# Mag_Enc_Sensors_muxed.net
KiCad netlist of a schematic drawn in Altium Designer
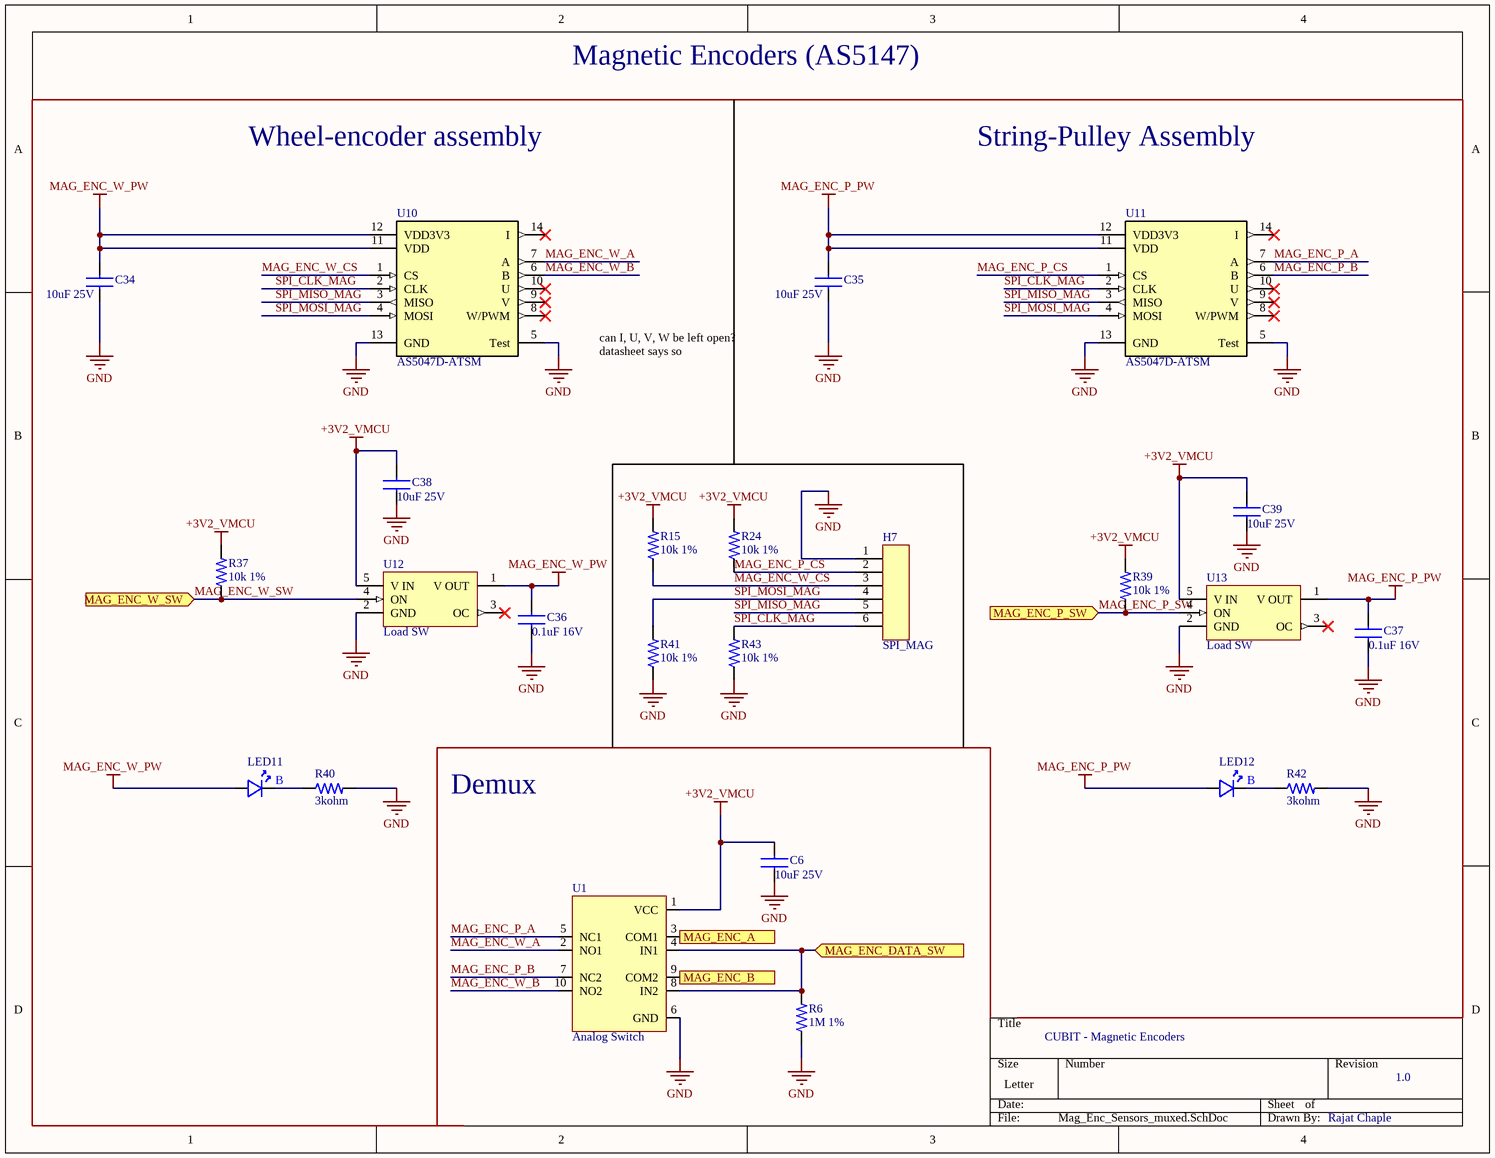
[diagram p0: Mag_Enc_Sensors_muxed.SchDoc]

(export (version "E")
  (design (tool "Eeschema 10.0.6"))
  (components
    (comp (ref "C6")
      (value "10uF 25V")
      (footprint "CAP_0805_02X125")
      (description "Cap 0805 25 V 10 uF ±20% Tolerance X5R Monolithic Ceramic Chip Capacitor")
      (fields
        (field (name "MANUFACTURER") "Murata")
        (field (name "MANUFACTURER PART NUMBER") "GRM21BR61E106KA73K")
      )
      (libsource (lib "LPEDT_proj_lib") (part "GRM21BR61E106KA73K"))
    )
    (comp (ref "C34")
      (value "10uF 25V")
      (footprint "CAP_0805_02X125")
      (description "Cap 0805 25 V 10 uF ±20% Tolerance X5R Monolithic Ceramic Chip Capacitor")
      (fields
        (field (name "MANUFACTURER") "Murata")
        (field (name "MANUFACTURER PART NUMBER") "GRM21BR61E106KA73K")
      )
      (libsource (lib "LPEDT_proj_lib") (part "GRM21BR61E106KA73K"))
    )
    (comp (ref "C35")
      (value "10uF 25V")
      (footprint "CAP_0805_02X125")
      (description "Cap 0805 25 V 10 uF ±20% Tolerance X5R Monolithic Ceramic Chip Capacitor")
      (fields
        (field (name "MANUFACTURER") "Murata")
        (field (name "MANUFACTURER PART NUMBER") "GRM21BR61E106KA73K")
      )
      (libsource (lib "LPEDT_proj_lib") (part "GRM21BR61E106KA73K"))
    )
    (comp (ref "C36")
      (value "0.1uF 16V")
      (footprint "CAP_0603_1MM")
      (description "Cap Ceramic 0.1uF 16V X7R 10% SMD 0603 125°C Paper T/R")
      (fields
        (field (name "MANUFACTURER") "KEMET")
        (field (name "MANUFACTURER PART NUMBER") "C0805C104K4RACAUTO")
      )
      (libsource (lib "LPEDT_proj_lib") (part "C0805C104K4RACAUTO"))
    )
    (comp (ref "C37")
      (value "0.1uF 16V")
      (footprint "CAP_0603_1MM")
      (description "Cap Ceramic 0.1uF 16V X7R 10% SMD 0603 125°C Paper T/R")
      (fields
        (field (name "MANUFACTURER") "KEMET")
        (field (name "MANUFACTURER PART NUMBER") "C0805C104K4RACAUTO")
      )
      (libsource (lib "LPEDT_proj_lib") (part "C0805C104K4RACAUTO"))
    )
    (comp (ref "C38")
      (value "10uF 25V")
      (footprint "CAP_0805_02X125")
      (description "Cap 0805 25 V 10 uF ±20% Tolerance X5R Monolithic Ceramic Chip Capacitor")
      (fields
        (field (name "MANUFACTURER") "Murata")
        (field (name "MANUFACTURER PART NUMBER") "GRM21BR61E106KA73K")
      )
      (libsource (lib "LPEDT_proj_lib") (part "GRM21BR61E106KA73K"))
    )
    (comp (ref "C39")
      (value "10uF 25V")
      (footprint "CAP_0805_02X125")
      (description "Cap 0805 25 V 10 uF ±20% Tolerance X5R Monolithic Ceramic Chip Capacitor")
      (fields
        (field (name "MANUFACTURER") "Murata")
        (field (name "MANUFACTURER PART NUMBER") "GRM21BR61E106KA73K")
      )
      (libsource (lib "LPEDT_proj_lib") (part "GRM21BR61E106KA73K"))
    )
    (comp (ref "H7")
      (value "SPI_MAG")
      (footprint "6_PIN_100MIL")
      (libsource (lib "LPEDT_proj_lib") (part "6_pin_connector"))
    )
    (comp (ref "LED11")
      (value "150060BS75000")
      (footprint "LED_0603_RED_WL-SMCW")
      (description "Led, Blue, 470 Nm, 3.2 V, 30 Ma, 145 Mcd Rohs Compliant: Yes")
      (fields (field (name "MANUFACTURER") "Wurth Electronics"))
      (libsource (lib "LPEDT_proj_lib") (part "150060BS75000"))
    )
    (comp (ref "LED12")
      (value "150060BS75000")
      (footprint "LED_0603_RED_WL-SMCW")
      (description "Led, Blue, 470 Nm, 3.2 V, 30 Ma, 145 Mcd Rohs Compliant: Yes")
      (fields (field (name "MANUFACTURER") "Wurth Electronics"))
      (libsource (lib "LPEDT_proj_lib") (part "150060BS75000"))
    )
    (comp (ref "R6")
      (value "1M 1%")
      (footprint "2_Chip_0603_RMCF")
      (description "Res 1M Ohm 1% 1/10W ±100ppm/°C Molded SMD Paper T/R")
      (fields
        (field (name "MANUFACTURER") "Stackpole Electronics")
        (field (name "MANUFACTURER PART NUMBER") "RMCF0603FT1M00")
      )
      (libsource (lib "LPEDT_proj_lib") (part "RMCF0603FT1M00"))
    )
    (comp (ref "R15")
      (value "10k 1%")
      (footprint "2_Chip_0603_RMCF")
      (description "Res 10K Ohm 1% 1/10W ±100ppm/°C Molded SMD SMD Paper T/R")
      (fields
        (field (name "MANUFACTURER") "Stackpole Electronics")
        (field (name "MANUFACTURER PART NUMBER") "RMCF0603FT10K0")
      )
      (libsource (lib "LPEDT_proj_lib") (part "RMCF0603FT10K0"))
    )
    (comp (ref "R24")
      (value "10k 1%")
      (footprint "2_Chip_0603_RMCF")
      (description "Res 10K Ohm 1% 1/10W ±100ppm/°C Molded SMD SMD Paper T/R")
      (fields
        (field (name "MANUFACTURER") "Stackpole Electronics")
        (field (name "MANUFACTURER PART NUMBER") "RMCF0603FT10K0")
      )
      (libsource (lib "LPEDT_proj_lib") (part "RMCF0603FT10K0"))
    )
    (comp (ref "R37")
      (value "10k 1%")
      (footprint "2_Chip_0603_RMCF")
      (description "Res 10K Ohm 1% 1/10W ±100ppm/°C Molded SMD SMD Paper T/R")
      (fields
        (field (name "MANUFACTURER") "Stackpole Electronics")
        (field (name "MANUFACTURER PART NUMBER") "RMCF0603FT10K0")
      )
      (libsource (lib "LPEDT_proj_lib") (part "RMCF0603FT10K0"))
    )
    (comp (ref "R39")
      (value "10k 1%")
      (footprint "2_Chip_0603_RMCF")
      (description "Res 10K Ohm 1% 1/10W ±100ppm/°C Molded SMD SMD Paper T/R")
      (fields
        (field (name "MANUFACTURER") "Stackpole Electronics")
        (field (name "MANUFACTURER PART NUMBER") "RMCF0603FT10K0")
      )
      (libsource (lib "LPEDT_proj_lib") (part "RMCF0603FT10K0"))
    )
    (comp (ref "R40")
      (value "3kohm")
      (footprint "CAP_0603_1MM")
      (description "Res 3000Ω ± 1.00% 0.1W ± 100ppm/℃ 0603")
      (fields
        (field (name "MANUFACTURER") "Yageo")
        (field (name "MANUFACTURER PART NUMBER") "RC0603FR-073KL")
      )
      (libsource (lib "LPEDT_proj_lib") (part "RC0603FR-073KL"))
    )
    (comp (ref "R41")
      (value "10k 1%")
      (footprint "2_Chip_0603_RMCF")
      (description "Res 10K Ohm 1% 1/10W ±100ppm/°C Molded SMD SMD Paper T/R")
      (fields
        (field (name "MANUFACTURER") "Stackpole Electronics")
        (field (name "MANUFACTURER PART NUMBER") "RMCF0603FT10K0")
      )
      (libsource (lib "LPEDT_proj_lib") (part "RMCF0603FT10K0"))
    )
    (comp (ref "R42")
      (value "3kohm")
      (footprint "CAP_0603_1MM")
      (description "Res 3000Ω ± 1.00% 0.1W ± 100ppm/℃ 0603")
      (fields
        (field (name "MANUFACTURER") "Yageo")
        (field (name "MANUFACTURER PART NUMBER") "RC0603FR-073KL")
      )
      (libsource (lib "LPEDT_proj_lib") (part "RC0603FR-073KL"))
    )
    (comp (ref "R43")
      (value "10k 1%")
      (footprint "2_Chip_0603_RMCF")
      (description "Res 10K Ohm 1% 1/10W ±100ppm/°C Molded SMD SMD Paper T/R")
      (fields
        (field (name "MANUFACTURER") "Stackpole Electronics")
        (field (name "MANUFACTURER PART NUMBER") "RMCF0603FT10K0")
      )
      (libsource (lib "LPEDT_proj_lib") (part "RMCF0603FT10K0"))
    )
    (comp (ref "U1")
      (value "Analog Switch")
      (footprint "TSSOP50P490X110-10N")
      (description "SPDT, 2 Func, 2 Channel, PDSO10")
      (fields
        (field (name "MANUFACTURER") "Texas Instruments")
        (field (name "MANUFACTURER PART NUMBER") "TS3A24159DGSR")
      )
      (libsource (lib "LPEDT_proj_lib") (part "TS3A24159DGSR"))
    )
    (comp (ref "U10")
      (value "AS5047D-ATSM")
      (footprint "14-TSOP_5x4_4")
      (fields (field (name "MANUFACTURER") "Osram"))
      (libsource (lib "LPEDT_proj_lib") (part "AS5047D-ATSM"))
    )
    (comp (ref "U11")
      (value "AS5047D-ATSM")
      (footprint "14-TSOP_5x4_4")
      (fields (field (name "MANUFACTURER") "Osram"))
      (libsource (lib "LPEDT_proj_lib") (part "AS5047D-ATSM"))
    )
    (comp (ref "U12")
      (value "Load SW")
      (footprint "SOT65P210X110-5N")
      (description "5.5-V, 0.1-A, 500-mΩ, load switch with current limit and active low enable 5-SC70 -40 to 85")
      (fields
        (field (name "MANUFACTURER") "Texas Instruments")
        (field (name "MANUFACTURER PART NUMBER") "TPS22942DCKR")
      )
      (libsource (lib "LPEDT_proj_lib") (part "TPS22942DCKR"))
    )
    (comp (ref "U13")
      (value "Load SW")
      (footprint "SOT65P210X110-5N")
      (description "5.5-V, 0.1-A, 500-mΩ, load switch with current limit and active low enable 5-SC70 -40 to 85")
      (fields
        (field (name "MANUFACTURER") "Texas Instruments")
        (field (name "MANUFACTURER PART NUMBER") "TPS22942DCKR")
      )
      (libsource (lib "LPEDT_proj_lib") (part "TPS22942DCKR"))
    )
  )
  (nets
    (net (code "1") (name "+3V2_VMCU") (class "Default")
      (node (ref "C38") (pin "1") (pinfunction "1_1") (pintype "passive"))
      (node (ref "C39") (pin "1") (pinfunction "1_1") (pintype "passive"))
      (node (ref "C6") (pin "1") (pinfunction "1_1") (pintype "passive"))
      (node (ref "R15") (pin "2") (pinfunction "2_2") (pintype "passive"))
      (node (ref "R24") (pin "2") (pinfunction "2_2") (pintype "passive"))
      (node (ref "R37") (pin "2") (pinfunction "2_2") (pintype "passive"))
      (node (ref "R39") (pin "2") (pinfunction "2_2") (pintype "passive"))
      (node (ref "U1") (pin "1") (pinfunction "VCC_1") (pintype "power_in"))
      (node (ref "U12") (pin "5") (pinfunction "V_IN_5") (pintype "power_in"))
      (node (ref "U13") (pin "5") (pinfunction "V_IN_5") (pintype "power_in"))
    )
    (net (code "2") (name "/MAG_ENC_A") (class "Default")
      (node (ref "U1") (pin "3") (pinfunction "COM1_3") (pintype "passive"))
    )
    (net (code "3") (name "/MAG_ENC_B") (class "Default")
      (node (ref "U1") (pin "9") (pinfunction "COM2_9") (pintype "passive"))
    )
    (net (code "4") (name "/MAG_ENC_DATA_SW") (class "Default")
      (node (ref "R6") (pin "2") (pinfunction "2_2") (pintype "passive"))
      (node (ref "U1") (pin "4") (pinfunction "IN1_4") (pintype "passive"))
      (node (ref "U1") (pin "8") (pinfunction "IN2_8") (pintype "passive"))
    )
    (net (code "5") (name "/MAG_ENC_P_A") (class "Default")
      (node (ref "U1") (pin "5") (pinfunction "NC1_5") (pintype "passive"))
      (node (ref "U11") (pin "7") (pinfunction "A_7") (pintype "output"))
    )
    (net (code "6") (name "/MAG_ENC_P_B") (class "Default")
      (node (ref "U1") (pin "7") (pinfunction "NC2_7") (pintype "passive"))
      (node (ref "U11") (pin "6") (pinfunction "B_6") (pintype "output"))
    )
    (net (code "7") (name "/MAG_ENC_P_CS") (class "Default")
      (node (ref "H7") (pin "2") (pintype "passive"))
      (node (ref "R24") (pin "1") (pinfunction "1_1") (pintype "passive"))
      (node (ref "U11") (pin "1") (pinfunction "CS_1") (pintype "input"))
    )
    (net (code "8") (name "/MAG_ENC_P_SW") (class "Default")
      (node (ref "R39") (pin "1") (pinfunction "1_1") (pintype "passive"))
      (node (ref "U13") (pin "4") (pinfunction "ON_4") (pintype "input"))
    )
    (net (code "9") (name "/MAG_ENC_W_A") (class "Default")
      (node (ref "U1") (pin "2") (pinfunction "NO1_2") (pintype "passive"))
      (node (ref "U10") (pin "7") (pinfunction "A_7") (pintype "output"))
    )
    (net (code "10") (name "/MAG_ENC_W_B") (class "Default")
      (node (ref "U1") (pin "10") (pinfunction "NO2_10") (pintype "passive"))
      (node (ref "U10") (pin "6") (pinfunction "B_6") (pintype "output"))
    )
    (net (code "11") (name "/MAG_ENC_W_CS") (class "Default")
      (node (ref "H7") (pin "3") (pintype "passive"))
      (node (ref "R15") (pin "1") (pinfunction "1_1") (pintype "passive"))
      (node (ref "U10") (pin "1") (pinfunction "CS_1") (pintype "input"))
    )
    (net (code "12") (name "/MAG_ENC_W_SW") (class "Default")
      (node (ref "R37") (pin "1") (pinfunction "1_1") (pintype "passive"))
      (node (ref "U12") (pin "4") (pinfunction "ON_4") (pintype "input"))
    )
    (net (code "13") (name "/SPI_CLK_MAG") (class "Default")
      (node (ref "H7") (pin "6") (pintype "power_in"))
      (node (ref "R43") (pin "2") (pinfunction "2_2") (pintype "passive"))
      (node (ref "U10") (pin "2") (pinfunction "CLK_2") (pintype "input"))
      (node (ref "U11") (pin "2") (pinfunction "CLK_2") (pintype "input"))
    )
    (net (code "14") (name "/SPI_MISO_MAG") (class "Default")
      (node (ref "H7") (pin "5") (pintype "passive"))
      (node (ref "U10") (pin "3") (pinfunction "MISO_3") (pintype "output"))
      (node (ref "U11") (pin "3") (pinfunction "MISO_3") (pintype "output"))
    )
    (net (code "15") (name "/SPI_MOSI_MAG") (class "Default")
      (node (ref "H7") (pin "4") (pintype "passive"))
      (node (ref "R41") (pin "2") (pinfunction "2_2") (pintype "passive"))
      (node (ref "U10") (pin "4") (pinfunction "MOSI_4") (pintype "input"))
      (node (ref "U11") (pin "4") (pinfunction "MOSI_4") (pintype "input"))
    )
    (net (code "16") (name "GND") (class "Default")
      (node (ref "C34") (pin "2") (pinfunction "2_2") (pintype "passive"))
      (node (ref "C35") (pin "2") (pinfunction "2_2") (pintype "passive"))
      (node (ref "C36") (pin "2") (pinfunction "2_2") (pintype "passive"))
      (node (ref "C37") (pin "2") (pinfunction "2_2") (pintype "passive"))
      (node (ref "C38") (pin "2") (pinfunction "2_2") (pintype "passive"))
      (node (ref "C39") (pin "2") (pinfunction "2_2") (pintype "passive"))
      (node (ref "C6") (pin "2") (pinfunction "2_2") (pintype "passive"))
      (node (ref "H7") (pin "1") (pintype "power_in"))
      (node (ref "R40") (pin "2") (pinfunction "2_2") (pintype "passive"))
      (node (ref "R41") (pin "1") (pinfunction "1_1") (pintype "passive"))
      (node (ref "R42") (pin "2") (pinfunction "2_2") (pintype "passive"))
      (node (ref "R43") (pin "1") (pinfunction "1_1") (pintype "passive"))
      (node (ref "R6") (pin "1") (pinfunction "1_1") (pintype "passive"))
      (node (ref "U1") (pin "6") (pinfunction "GND_6") (pintype "power_in"))
      (node (ref "U10") (pin "13") (pinfunction "GND_13") (pintype "power_in"))
      (node (ref "U10") (pin "5") (pinfunction "Test_5") (pintype "passive"))
      (node (ref "U11") (pin "13") (pinfunction "GND_13") (pintype "power_in"))
      (node (ref "U11") (pin "5") (pinfunction "Test_5") (pintype "passive"))
      (node (ref "U12") (pin "2") (pinfunction "GND_2") (pintype "power_in"))
      (node (ref "U13") (pin "2") (pinfunction "GND_2") (pintype "power_in"))
    )
    (net (code "17") (name "MAG_ENC_P_PW") (class "Default")
      (node (ref "C35") (pin "1") (pinfunction "1_1") (pintype "passive"))
      (node (ref "C37") (pin "1") (pinfunction "1_1") (pintype "passive"))
      (node (ref "LED12") (pin "A") (pinfunction "A_A") (pintype "passive"))
      (node (ref "U11") (pin "11") (pinfunction "VDD_11") (pintype "power_in"))
      (node (ref "U11") (pin "12") (pinfunction "VDD3V3_12") (pintype "power_in"))
      (node (ref "U13") (pin "1") (pinfunction "V_OUT_1") (pintype "power_in"))
    )
    (net (code "18") (name "MAG_ENC_W_PW") (class "Default")
      (node (ref "C34") (pin "1") (pinfunction "1_1") (pintype "passive"))
      (node (ref "C36") (pin "1") (pinfunction "1_1") (pintype "passive"))
      (node (ref "LED11") (pin "A") (pinfunction "A_A") (pintype "passive"))
      (node (ref "U10") (pin "11") (pinfunction "VDD_11") (pintype "power_in"))
      (node (ref "U10") (pin "12") (pinfunction "VDD3V3_12") (pintype "power_in"))
      (node (ref "U12") (pin "1") (pinfunction "V_OUT_1") (pintype "power_in"))
    )
    (net (code "19") (name "Net-(LED11-PadC)") (class "Default")
      (node (ref "LED11") (pin "C") (pinfunction "C_C") (pintype "passive"))
      (node (ref "R40") (pin "1") (pinfunction "1_1") (pintype "passive"))
    )
    (net (code "20") (name "Net-(LED12-PadC)") (class "Default")
      (node (ref "LED12") (pin "C") (pinfunction "C_C") (pintype "passive"))
      (node (ref "R42") (pin "1") (pinfunction "1_1") (pintype "passive"))
    )
    (net (code "21") (name "unconnected-(U10-I-Pad14)") (class "Default")
      (node (ref "U10") (pin "14") (pinfunction "I_14") (pintype "output+no_connect"))
    )
    (net (code "22") (name "unconnected-(U10-U-Pad10)") (class "Default")
      (node (ref "U10") (pin "10") (pinfunction "U_10") (pintype "output+no_connect"))
    )
    (net (code "23") (name "unconnected-(U10-V-Pad9)") (class "Default")
      (node (ref "U10") (pin "9") (pinfunction "V_9") (pintype "output+no_connect"))
    )
    (net (code "24") (name "unconnected-(U10-W{slash}PWM-Pad8)") (class "Default")
      (node (ref "U10") (pin "8") (pinfunction "W/PWM_8") (pintype "output+no_connect"))
    )
    (net (code "25") (name "unconnected-(U11-I-Pad14)") (class "Default")
      (node (ref "U11") (pin "14") (pinfunction "I_14") (pintype "output+no_connect"))
    )
    (net (code "26") (name "unconnected-(U11-U-Pad10)") (class "Default")
      (node (ref "U11") (pin "10") (pinfunction "U_10") (pintype "output+no_connect"))
    )
    (net (code "27") (name "unconnected-(U11-V-Pad9)") (class "Default")
      (node (ref "U11") (pin "9") (pinfunction "V_9") (pintype "output+no_connect"))
    )
    (net (code "28") (name "unconnected-(U11-W{slash}PWM-Pad8)") (class "Default")
      (node (ref "U11") (pin "8") (pinfunction "W/PWM_8") (pintype "output+no_connect"))
    )
    (net (code "29") (name "unconnected-(U12-OC-Pad3)") (class "Default")
      (node (ref "U12") (pin "3") (pinfunction "OC_3") (pintype "output+no_connect"))
    )
    (net (code "30") (name "unconnected-(U13-OC-Pad3)") (class "Default")
      (node (ref "U13") (pin "3") (pinfunction "OC_3") (pintype "output+no_connect"))
    )
  )
)
